# vga_fpga.net
KiCad netlist of a schematic drawn in EAGLE
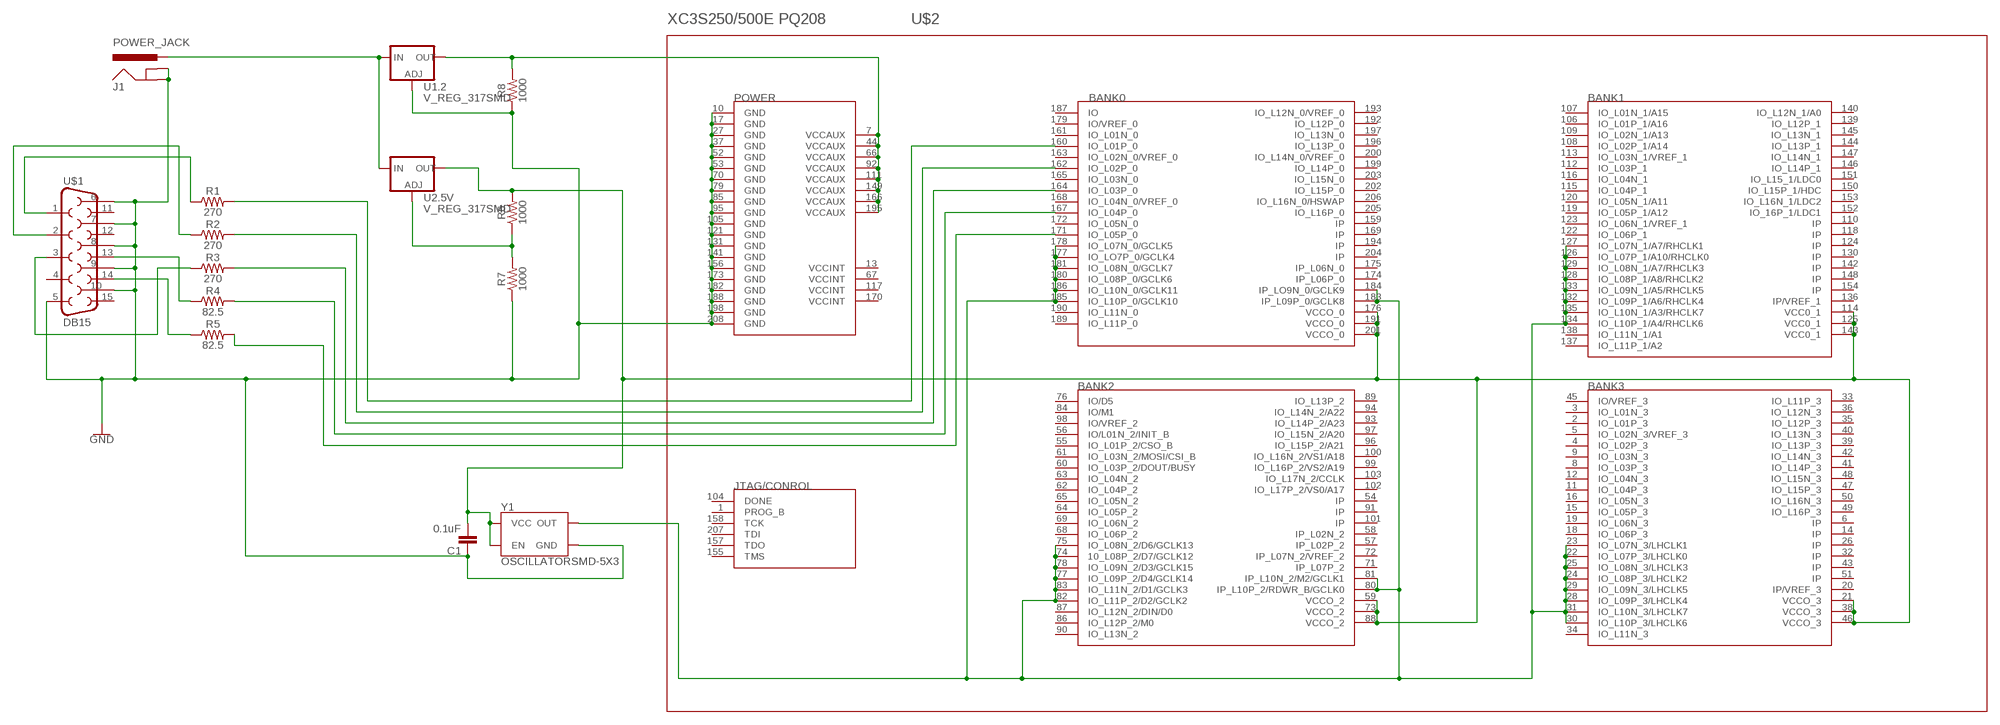
[diagram p0: schematic, sheet 1]

(export (version "E")
  (design (tool "Eeschema 10.0.6"))
  (components
    (comp (ref "C1")
      (value "0.1uF")
      (footprint "eagle-import:0603")
      (libsource (lib "eagle-import") (part "0.1UF-0603-25V-(+80/-20%)"))
    )
    (comp (ref "J1")
      (value "POWER_JACK")
      (footprint "eagle-import:POWER_JACK_PTH")
      (libsource (lib "eagle-import") (part "POWER_JACK"))
    )
    (comp (ref "R1")
      (value "270")
      (footprint "eagle-import:0603")
      (libsource (lib "eagle-import") (part "RESISTOR0603"))
    )
    (comp (ref "R2")
      (value "270")
      (footprint "eagle-import:0603")
      (libsource (lib "eagle-import") (part "RESISTOR0603"))
    )
    (comp (ref "R3")
      (value "270")
      (footprint "eagle-import:0603")
      (libsource (lib "eagle-import") (part "RESISTOR0603"))
    )
    (comp (ref "R4")
      (value "82.5")
      (footprint "eagle-import:0603")
      (libsource (lib "eagle-import") (part "RESISTOR0603"))
    )
    (comp (ref "R5")
      (value "82.5")
      (footprint "eagle-import:0603")
      (libsource (lib "eagle-import") (part "RESISTOR0603"))
    )
    (comp (ref "R6")
      (value "1000")
      (footprint "eagle-import:0603")
      (libsource (lib "eagle-import") (part "RESISTOR0603"))
    )
    (comp (ref "R7")
      (value "1000")
      (footprint "eagle-import:0603")
      (libsource (lib "eagle-import") (part "RESISTOR0603"))
    )
    (comp (ref "R8")
      (value "1000")
      (footprint "eagle-import:0603")
      (libsource (lib "eagle-import") (part "RESISTOR0603"))
    )
    (comp (ref "U$1")
      (value "DB15")
      (footprint "eagle-import:DB15")
      (libsource (lib "eagle-import") (part "DB15"))
    )
    (comp (ref "U$2")
      (value "XC3S250/500E-PQ208")
      (footprint "eagle-import:PQ208")
      (libsource (lib "eagle-import") (part "XC3S250/500E-PQ208"))
    )
    (comp (ref "U1.2")
      (value "V_REG_317SMD")
      (footprint "eagle-import:SOT223")
      (libsource (lib "eagle-import") (part "V_REG_317SMD"))
    )
    (comp (ref "U2.5V")
      (value "V_REG_317SMD")
      (footprint "eagle-import:SOT223")
      (libsource (lib "eagle-import") (part "V_REG_317SMD"))
    )
    (comp (ref "Y1")
      (value "OSCILLATORSMD-5X3")
      (footprint "eagle-import:OSCILLATOR-SMD-5X3.2")
      (libsource (lib "eagle-import") (part "OSCILLATORSMD-5X3"))
    )
  )
  (nets
    (net (code "1") (name "GND") (class "Default")
      (node (ref "C1") (pin "1") (pinfunction "1_1") (pintype "passive"))
      (node (ref "J1") (pin "GND") (pinfunction "GND_GND") (pintype "bidirectional"))
      (node (ref "J1") (pin "GNDBREAK") (pinfunction "GNDBREAK_GNDBREAK") (pintype "bidirectional"))
      (node (ref "R7") (pin "1") (pinfunction "1_1") (pintype "passive"))
      (node (ref "R8") (pin "1") (pinfunction "1_1") (pintype "passive"))
      (node (ref "U$1") (pin "10") (pinfunction "10_10") (pintype "passive"))
      (node (ref "U$1") (pin "5") (pinfunction "5_5") (pintype "passive"))
      (node (ref "U$1") (pin "6") (pinfunction "6_6") (pintype "passive"))
      (node (ref "U$1") (pin "7") (pinfunction "7_7") (pintype "passive"))
      (node (ref "U$1") (pin "8") (pinfunction "8_8") (pintype "passive"))
      (node (ref "U$1") (pin "9") (pinfunction "9_9") (pintype "passive"))
      (node (ref "U$2") (pin "10") (pinfunction "GND_10") (pintype "bidirectional"))
      (node (ref "U$2") (pin "105") (pinfunction "GND_105") (pintype "bidirectional"))
      (node (ref "U$2") (pin "121") (pinfunction "GND_121") (pintype "bidirectional"))
      (node (ref "U$2") (pin "131") (pinfunction "GND_131") (pintype "bidirectional"))
      (node (ref "U$2") (pin "141") (pinfunction "GND_141") (pintype "bidirectional"))
      (node (ref "U$2") (pin "156") (pinfunction "GND_156") (pintype "bidirectional"))
      (node (ref "U$2") (pin "17") (pinfunction "GND_17") (pintype "bidirectional"))
      (node (ref "U$2") (pin "173") (pinfunction "GND_173") (pintype "bidirectional"))
      (node (ref "U$2") (pin "182") (pinfunction "GND_182") (pintype "bidirectional"))
      (node (ref "U$2") (pin "188") (pinfunction "GND_188") (pintype "bidirectional"))
      (node (ref "U$2") (pin "198") (pinfunction "GND_198") (pintype "bidirectional"))
      (node (ref "U$2") (pin "208") (pinfunction "GND_208") (pintype "bidirectional"))
      (node (ref "U$2") (pin "27") (pinfunction "GND_27") (pintype "bidirectional"))
      (node (ref "U$2") (pin "37") (pinfunction "GND_37") (pintype "bidirectional"))
      (node (ref "U$2") (pin "52") (pinfunction "GND_52") (pintype "bidirectional"))
      (node (ref "U$2") (pin "53") (pinfunction "GND_53") (pintype "bidirectional"))
      (node (ref "U$2") (pin "70") (pinfunction "GND_70") (pintype "bidirectional"))
      (node (ref "U$2") (pin "79") (pinfunction "GND_79") (pintype "bidirectional"))
      (node (ref "U$2") (pin "85") (pinfunction "GND_85") (pintype "bidirectional"))
      (node (ref "U$2") (pin "95") (pinfunction "GND_95") (pintype "bidirectional"))
      (node (ref "U1.2") (pin "1") (pinfunction "ADJ_1") (pintype "input"))
      (node (ref "Y1") (pin "2") (pinfunction "GND_2") (pintype "bidirectional"))
    )
    (net (code "2") (name "Net-(R1-Pad1)") (class "Default")
      (node (ref "R1") (pin "1") (pinfunction "1_1") (pintype "passive"))
      (node (ref "U$1") (pin "1") (pinfunction "1_1") (pintype "passive"))
    )
    (net (code "3") (name "Net-(R2-Pad1)") (class "Default")
      (node (ref "R2") (pin "1") (pinfunction "1_1") (pintype "passive"))
      (node (ref "U$1") (pin "2") (pinfunction "2_2") (pintype "passive"))
    )
    (net (code "4") (name "Net-(R3-Pad1)") (class "Default")
      (node (ref "R3") (pin "1") (pinfunction "1_1") (pintype "passive"))
      (node (ref "U$1") (pin "3") (pinfunction "3_3") (pintype "passive"))
    )
    (net (code "5") (name "Net-(R4-Pad1)") (class "Default")
      (node (ref "R4") (pin "1") (pinfunction "1_1") (pintype "passive"))
      (node (ref "U$1") (pin "13") (pinfunction "13_13") (pintype "passive"))
    )
    (net (code "6") (name "Net-(R5-Pad1)") (class "Default")
      (node (ref "R5") (pin "1") (pinfunction "1_1") (pintype "passive"))
      (node (ref "U$1") (pin "14") (pinfunction "14_14") (pintype "passive"))
    )
    (net (code "7") (name "Net-(U$2-10_L08P_2{slash}D7{slash}GCLK12)") (class "Default")
      (node (ref "U$2") (pin "126") (pinfunction "IO_L07P_1/A10/RHCLK0_126") (pintype "bidirectional"))
      (node (ref "U$2") (pin "127") (pinfunction "IO_L07N_1/A7/RHCLK1_127") (pintype "bidirectional"))
      (node (ref "U$2") (pin "128") (pinfunction "IO_L08P_1/A8/RHCLK2_128") (pintype "bidirectional"))
      (node (ref "U$2") (pin "129") (pinfunction "IO_L08N_1/A7/RHCLK3_129") (pintype "bidirectional"))
      (node (ref "U$2") (pin "132") (pinfunction "IO_L09P_1/A6/RHCLK4_132") (pintype "bidirectional"))
      (node (ref "U$2") (pin "133") (pinfunction "IO_L09N_1/A5/RHCLK5_133") (pintype "bidirectional"))
      (node (ref "U$2") (pin "134") (pinfunction "IO_L10P_1/A4/RHCLK6_134") (pintype "bidirectional"))
      (node (ref "U$2") (pin "135") (pinfunction "IO_L10N_1/A3/RHCLK7_135") (pintype "bidirectional"))
      (node (ref "U$2") (pin "177") (pinfunction "IO_LO7P_0/GCLK4_177") (pintype "bidirectional"))
      (node (ref "U$2") (pin "178") (pinfunction "IO_L07N_0/GCLK5_178") (pintype "bidirectional"))
      (node (ref "U$2") (pin "180") (pinfunction "IO_L08P_0/GCLK6_180") (pintype "bidirectional"))
      (node (ref "U$2") (pin "181") (pinfunction "IO_L08N_0/GCLK7_181") (pintype "bidirectional"))
      (node (ref "U$2") (pin "183") (pinfunction "IP_L09P_0/GCLK8_183") (pintype "bidirectional"))
      (node (ref "U$2") (pin "184") (pinfunction "IP_LO9N_0/GCLK9_184") (pintype "bidirectional"))
      (node (ref "U$2") (pin "185") (pinfunction "IO_L10P_0/GCLK10_185") (pintype "bidirectional"))
      (node (ref "U$2") (pin "186") (pinfunction "IO_L10N_0/GCLK11_186") (pintype "bidirectional"))
      (node (ref "U$2") (pin "22") (pinfunction "IO_L07P_3/LHCLK0_22") (pintype "bidirectional"))
      (node (ref "U$2") (pin "23") (pinfunction "IO_L07N_3/LHCLK1_23") (pintype "bidirectional"))
      (node (ref "U$2") (pin "24") (pinfunction "IO_L08P_3/LHCLK2_24") (pintype "bidirectional"))
      (node (ref "U$2") (pin "25") (pinfunction "IO_L08N_3/LHCLK3_25") (pintype "bidirectional"))
      (node (ref "U$2") (pin "28") (pinfunction "IO_L09P_3/LHCLK4_28") (pintype "bidirectional"))
      (node (ref "U$2") (pin "29") (pinfunction "IO_L09N_3/LHCLK5_29") (pintype "bidirectional"))
      (node (ref "U$2") (pin "30") (pinfunction "IO_L10P_3/LHCLK6_30") (pintype "bidirectional"))
      (node (ref "U$2") (pin "31") (pinfunction "IO_L10N_3/LHCLK7_31") (pintype "bidirectional"))
      (node (ref "U$2") (pin "74") (pinfunction "10_L08P_2/D7/GCLK12_74") (pintype "bidirectional"))
      (node (ref "U$2") (pin "75") (pinfunction "IO_L08N_2/D6/GCLK13_75") (pintype "bidirectional"))
      (node (ref "U$2") (pin "77") (pinfunction "IO_L09P_2/D4/GCLK14_77") (pintype "bidirectional"))
      (node (ref "U$2") (pin "78") (pinfunction "IO_L09N_2/D3/GCLK15_78") (pintype "bidirectional"))
      (node (ref "U$2") (pin "80") (pinfunction "IP_L10P_2/RDWR_B/GCLK0_80") (pintype "bidirectional"))
      (node (ref "U$2") (pin "81") (pinfunction "IP_L10N_2/M2/GCLK1_81") (pintype "bidirectional"))
      (node (ref "U$2") (pin "82") (pinfunction "IO_L11P_2/D2/GCLK2_82") (pintype "bidirectional"))
      (node (ref "U$2") (pin "83") (pinfunction "IO_L11N_2/D1/GCLK3_83") (pintype "bidirectional"))
      (node (ref "Y1") (pin "3") (pinfunction "OUT_3") (pintype "bidirectional"))
    )
    (net (code "8") (name "Net-(U$2-IO_L01P_0)") (class "Default")
      (node (ref "R1") (pin "2") (pinfunction "2_2") (pintype "passive"))
      (node (ref "U$2") (pin "160") (pinfunction "IO_L01P_0_160") (pintype "bidirectional"))
    )
    (net (code "9") (name "Net-(U$2-IO_L02P_0)") (class "Default")
      (node (ref "R2") (pin "2") (pinfunction "2_2") (pintype "passive"))
      (node (ref "U$2") (pin "162") (pinfunction "IO_L02P_0_162") (pintype "bidirectional"))
    )
    (net (code "10") (name "Net-(U$2-IO_L03P_0)") (class "Default")
      (node (ref "R3") (pin "2") (pinfunction "2_2") (pintype "passive"))
      (node (ref "U$2") (pin "164") (pinfunction "IO_L03P_0_164") (pintype "bidirectional"))
    )
    (net (code "11") (name "Net-(U$2-IO_L04P_0)") (class "Default")
      (node (ref "R4") (pin "2") (pinfunction "2_2") (pintype "passive"))
      (node (ref "U$2") (pin "167") (pinfunction "IO_L04P_0_167") (pintype "bidirectional"))
    )
    (net (code "12") (name "Net-(U$2-IO_L05P_0)") (class "Default")
      (node (ref "R5") (pin "2") (pinfunction "2_2") (pintype "passive"))
      (node (ref "U$2") (pin "171") (pinfunction "IO_L05P_0_171") (pintype "bidirectional"))
    )
    (net (code "13") (name "Net-(U1.2-IN)") (class "Default")
      (node (ref "J1") (pin "PWR") (pinfunction "PWR_PWR") (pintype "bidirectional"))
      (node (ref "U1.2") (pin "3") (pinfunction "IN_3") (pintype "input"))
      (node (ref "U2.5V") (pin "3") (pinfunction "IN_3") (pintype "input"))
    )
    (net (code "14") (name "Net-(U1.2-OUT)") (class "Default")
      (node (ref "R8") (pin "2") (pinfunction "2_2") (pintype "passive"))
      (node (ref "U$2") (pin "111") (pinfunction "VCCAUX_111") (pintype "bidirectional"))
      (node (ref "U$2") (pin "149") (pinfunction "VCCAUX_149") (pintype "bidirectional"))
      (node (ref "U$2") (pin "166") (pinfunction "VCCAUX_166") (pintype "bidirectional"))
      (node (ref "U$2") (pin "195") (pinfunction "VCCAUX_195") (pintype "bidirectional"))
      (node (ref "U$2") (pin "44") (pinfunction "VCCAUX_44") (pintype "bidirectional"))
      (node (ref "U$2") (pin "66") (pinfunction "VCCAUX_66") (pintype "bidirectional"))
      (node (ref "U$2") (pin "7") (pinfunction "VCCAUX_7") (pintype "bidirectional"))
      (node (ref "U$2") (pin "92") (pinfunction "VCCAUX_92") (pintype "bidirectional"))
      (node (ref "U1.2") (pin "2") (pinfunction "OUT_2") (pintype "output"))
    )
    (net (code "15") (name "Net-(U2.5V-ADJ)") (class "Default")
      (node (ref "R6") (pin "1") (pinfunction "1_1") (pintype "passive"))
      (node (ref "R7") (pin "2") (pinfunction "2_2") (pintype "passive"))
      (node (ref "U2.5V") (pin "1") (pinfunction "ADJ_1") (pintype "input"))
    )
    (net (code "16") (name "Net-(U2.5V-OUT)") (class "Default")
      (node (ref "C1") (pin "2") (pinfunction "2_2") (pintype "passive"))
      (node (ref "R6") (pin "2") (pinfunction "2_2") (pintype "passive"))
      (node (ref "U$2") (pin "114") (pinfunction "VCC0_1_114") (pintype "bidirectional"))
      (node (ref "U$2") (pin "125") (pinfunction "VCC0_1_125") (pintype "bidirectional"))
      (node (ref "U$2") (pin "143") (pinfunction "VCC0_1_143") (pintype "bidirectional"))
      (node (ref "U$2") (pin "176") (pinfunction "VCCO_0_176") (pintype "bidirectional"))
      (node (ref "U$2") (pin "191") (pinfunction "VCCO_0_191") (pintype "bidirectional"))
      (node (ref "U$2") (pin "201") (pinfunction "VCCO_0_201") (pintype "bidirectional"))
      (node (ref "U$2") (pin "21") (pinfunction "VCCO_3_21") (pintype "bidirectional"))
      (node (ref "U$2") (pin "38") (pinfunction "VCCO_3_38") (pintype "bidirectional"))
      (node (ref "U$2") (pin "46") (pinfunction "VCCO_3_46") (pintype "bidirectional"))
      (node (ref "U$2") (pin "59") (pinfunction "VCCO_2_59") (pintype "bidirectional"))
      (node (ref "U$2") (pin "73") (pinfunction "VCCO_2_73") (pintype "bidirectional"))
      (node (ref "U$2") (pin "88") (pinfunction "VCCO_2_88") (pintype "bidirectional"))
      (node (ref "U2.5V") (pin "2") (pinfunction "OUT_2") (pintype "output"))
      (node (ref "Y1") (pin "1") (pinfunction "EN_1") (pintype "bidirectional"))
      (node (ref "Y1") (pin "4") (pinfunction "VCC_4") (pintype "bidirectional"))
    )
    (net (code "17") (name "unconnected-(U$1-Pad4)") (class "Default")
      (node (ref "U$1") (pin "4") (pinfunction "4_4") (pintype "passive"))
    )
    (net (code "18") (name "unconnected-(U$1-Pad11)") (class "Default")
      (node (ref "U$1") (pin "11") (pinfunction "11_11") (pintype "passive"))
    )
    (net (code "19") (name "unconnected-(U$1-Pad12)") (class "Default")
      (node (ref "U$1") (pin "12") (pinfunction "12_12") (pintype "passive"))
    )
    (net (code "20") (name "unconnected-(U$1-Pad15)") (class "Default")
      (node (ref "U$1") (pin "15") (pinfunction "15_15") (pintype "passive"))
    )
    (net (code "21") (name "unconnected-(U$2-DONE-Pad104)") (class "Default")
      (node (ref "U$2") (pin "104") (pinfunction "DONE_104") (pintype "bidirectional"))
    )
    (net (code "22") (name "unconnected-(U$2-IO-Pad187)") (class "Default")
      (node (ref "U$2") (pin "187") (pinfunction "IO_187") (pintype "bidirectional"))
    )
    (net (code "23") (name "unconnected-(U$2-IO_16P_1{slash}LDC1-Pad152)") (class "Default")
      (node (ref "U$2") (pin "152") (pinfunction "IO_16P_1/LDC1_152") (pintype "bidirectional"))
    )
    (net (code "24") (name "unconnected-(U$2-IO_L01N_0-Pad161)") (class "Default")
      (node (ref "U$2") (pin "161") (pinfunction "IO_L01N_0_161") (pintype "bidirectional"))
    )
    (net (code "25") (name "unconnected-(U$2-IO_L01N_1{slash}A15-Pad107)") (class "Default")
      (node (ref "U$2") (pin "107") (pinfunction "IO_L01N_1/A15_107") (pintype "bidirectional"))
    )
    (net (code "26") (name "unconnected-(U$2-IO_L01N_3-Pad3)") (class "Default")
      (node (ref "U$2") (pin "3") (pinfunction "IO_L01N_3_3") (pintype "bidirectional"))
    )
    (net (code "27") (name "unconnected-(U$2-IO_L01P_1{slash}A16-Pad106)") (class "Default")
      (node (ref "U$2") (pin "106") (pinfunction "IO_L01P_1/A16_106") (pintype "bidirectional"))
    )
    (net (code "28") (name "unconnected-(U$2-IO_L01P_2{slash}CSO_B-Pad55)") (class "Default")
      (node (ref "U$2") (pin "55") (pinfunction "IO_L01P_2/CSO_B_55") (pintype "bidirectional"))
    )
    (net (code "29") (name "unconnected-(U$2-IO_L01P_3-Pad2)") (class "Default")
      (node (ref "U$2") (pin "2") (pinfunction "IO_L01P_3_2") (pintype "bidirectional"))
    )
    (net (code "30") (name "unconnected-(U$2-IO_L02N_0{slash}VREF_0-Pad163)") (class "Default")
      (node (ref "U$2") (pin "163") (pinfunction "IO_L02N_0/VREF_0_163") (pintype "bidirectional"))
    )
    (net (code "31") (name "unconnected-(U$2-IO_L02N_1{slash}A13-Pad109)") (class "Default")
      (node (ref "U$2") (pin "109") (pinfunction "IO_L02N_1/A13_109") (pintype "bidirectional"))
    )
    (net (code "32") (name "unconnected-(U$2-IO_L02N_3{slash}VREF_3-Pad5)") (class "Default")
      (node (ref "U$2") (pin "5") (pinfunction "IO_L02N_3/VREF_3_5") (pintype "bidirectional"))
    )
    (net (code "33") (name "unconnected-(U$2-IO_L02P_1{slash}A14-Pad108)") (class "Default")
      (node (ref "U$2") (pin "108") (pinfunction "IO_L02P_1/A14_108") (pintype "bidirectional"))
    )
    (net (code "34") (name "unconnected-(U$2-IO_L02P_3-Pad4)") (class "Default")
      (node (ref "U$2") (pin "4") (pinfunction "IO_L02P_3_4") (pintype "bidirectional"))
    )
    (net (code "35") (name "unconnected-(U$2-IO_L03N_0-Pad165)") (class "Default")
      (node (ref "U$2") (pin "165") (pinfunction "IO_L03N_0_165") (pintype "bidirectional"))
    )
    (net (code "36") (name "unconnected-(U$2-IO_L03N_1{slash}VREF_1-Pad113)") (class "Default")
      (node (ref "U$2") (pin "113") (pinfunction "IO_L03N_1/VREF_1_113") (pintype "bidirectional"))
    )
    (net (code "37") (name "unconnected-(U$2-IO_L03N_2{slash}MOSI{slash}CSI_B-Pad61)") (class "Default")
      (node (ref "U$2") (pin "61") (pinfunction "IO_L03N_2/MOSI/CSI_B_61") (pintype "bidirectional"))
    )
    (net (code "38") (name "unconnected-(U$2-IO_L03N_3-Pad9)") (class "Default")
      (node (ref "U$2") (pin "9") (pinfunction "IO_L03N_3_9") (pintype "bidirectional"))
    )
    (net (code "39") (name "unconnected-(U$2-IO_L03P_1-Pad112)") (class "Default")
      (node (ref "U$2") (pin "112") (pinfunction "IO_L03P_1_112") (pintype "bidirectional"))
    )
    (net (code "40") (name "unconnected-(U$2-IO_L03P_2{slash}DOUT{slash}BUSY-Pad60)") (class "Default")
      (node (ref "U$2") (pin "60") (pinfunction "IO_L03P_2/DOUT/BUSY_60") (pintype "bidirectional"))
    )
    (net (code "41") (name "unconnected-(U$2-IO_L03P_3-Pad8)") (class "Default")
      (node (ref "U$2") (pin "8") (pinfunction "IO_L03P_3_8") (pintype "bidirectional"))
    )
    (net (code "42") (name "unconnected-(U$2-IO_L04N_0{slash}VREF_0-Pad168)") (class "Default")
      (node (ref "U$2") (pin "168") (pinfunction "IO_L04N_0/VREF_0_168") (pintype "bidirectional"))
    )
    (net (code "43") (name "unconnected-(U$2-IO_L04N_1-Pad116)") (class "Default")
      (node (ref "U$2") (pin "116") (pinfunction "IO_L04N_1_116") (pintype "bidirectional"))
    )
    (net (code "44") (name "unconnected-(U$2-IO_L04N_2-Pad63)") (class "Default")
      (node (ref "U$2") (pin "63") (pinfunction "IO_L04N_2_63") (pintype "bidirectional"))
    )
    (net (code "45") (name "unconnected-(U$2-IO_L04N_3-Pad12)") (class "Default")
      (node (ref "U$2") (pin "12") (pinfunction "IO_L04N_3_12") (pintype "bidirectional"))
    )
    (net (code "46") (name "unconnected-(U$2-IO_L04P_1-Pad115)") (class "Default")
      (node (ref "U$2") (pin "115") (pinfunction "IO_L04P_1_115") (pintype "bidirectional"))
    )
    (net (code "47") (name "unconnected-(U$2-IO_L04P_2-Pad62)") (class "Default")
      (node (ref "U$2") (pin "62") (pinfunction "IO_L04P_2_62") (pintype "bidirectional"))
    )
    (net (code "48") (name "unconnected-(U$2-IO_L04P_3-Pad11)") (class "Default")
      (node (ref "U$2") (pin "11") (pinfunction "IO_L04P_3_11") (pintype "bidirectional"))
    )
    (net (code "49") (name "unconnected-(U$2-IO_L05N_0-Pad172)") (class "Default")
      (node (ref "U$2") (pin "172") (pinfunction "IO_L05N_0_172") (pintype "bidirectional"))
    )
    (net (code "50") (name "unconnected-(U$2-IO_L05N_1{slash}A11-Pad120)") (class "Default")
      (node (ref "U$2") (pin "120") (pinfunction "IO_L05N_1/A11_120") (pintype "bidirectional"))
    )
    (net (code "51") (name "unconnected-(U$2-IO_L05N_2-Pad65)") (class "Default")
      (node (ref "U$2") (pin "65") (pinfunction "IO_L05N_2_65") (pintype "bidirectional"))
    )
    (net (code "52") (name "unconnected-(U$2-IO_L05N_3-Pad16)") (class "Default")
      (node (ref "U$2") (pin "16") (pinfunction "IO_L05N_3_16") (pintype "bidirectional"))
    )
    (net (code "53") (name "unconnected-(U$2-IO_L05P_1{slash}A12-Pad119)") (class "Default")
      (node (ref "U$2") (pin "119") (pinfunction "IO_L05P_1/A12_119") (pintype "bidirectional"))
    )
    (net (code "54") (name "unconnected-(U$2-IO_L05P_2-Pad64)") (class "Default")
      (node (ref "U$2") (pin "64") (pinfunction "IO_L05P_2_64") (pintype "bidirectional"))
    )
    (net (code "55") (name "unconnected-(U$2-IO_L05P_3-Pad15)") (class "Default")
      (node (ref "U$2") (pin "15") (pinfunction "IO_L05P_3_15") (pintype "bidirectional"))
    )
    (net (code "56") (name "unconnected-(U$2-IO_L06N_1{slash}VREF_1-Pad123)") (class "Default")
      (node (ref "U$2") (pin "123") (pinfunction "IO_L06N_1/VREF_1_123") (pintype "bidirectional"))
    )
    (net (code "57") (name "unconnected-(U$2-IO_L06N_2-Pad69)") (class "Default")
      (node (ref "U$2") (pin "69") (pinfunction "IO_L06N_2_69") (pintype "bidirectional"))
    )
    (net (code "58") (name "unconnected-(U$2-IO_L06N_3-Pad19)") (class "Default")
      (node (ref "U$2") (pin "19") (pinfunction "IO_L06N_3_19") (pintype "bidirectional"))
    )
    (net (code "59") (name "unconnected-(U$2-IO_L06P_1-Pad122)") (class "Default")
      (node (ref "U$2") (pin "122") (pinfunction "IO_L06P_1_122") (pintype "bidirectional"))
    )
    (net (code "60") (name "unconnected-(U$2-IO_L06P_2-Pad68)") (class "Default")
      (node (ref "U$2") (pin "68") (pinfunction "IO_L06P_2_68") (pintype "bidirectional"))
    )
    (net (code "61") (name "unconnected-(U$2-IO_L06P_3-Pad18)") (class "Default")
      (node (ref "U$2") (pin "18") (pinfunction "IO_L06P_3_18") (pintype "bidirectional"))
    )
    (net (code "62") (name "unconnected-(U$2-IO_L11N_0-Pad190)") (class "Default")
      (node (ref "U$2") (pin "190") (pinfunction "IO_L11N_0_190") (pintype "bidirectional"))
    )
    (net (code "63") (name "unconnected-(U$2-IO_L11N_1{slash}A1-Pad138)") (class "Default")
      (node (ref "U$2") (pin "138") (pinfunction "IO_L11N_1/A1_138") (pintype "bidirectional"))
    )
    (net (code "64") (name "unconnected-(U$2-IO_L11N_3-Pad34)") (class "Default")
      (node (ref "U$2") (pin "34") (pinfunction "IO_L11N_3_34") (pintype "bidirectional"))
    )
    (net (code "65") (name "unconnected-(U$2-IO_L11P_0-Pad189)") (class "Default")
      (node (ref "U$2") (pin "189") (pinfunction "IO_L11P_0_189") (pintype "bidirectional"))
    )
    (net (code "66") (name "unconnected-(U$2-IO_L11P_1{slash}A2-Pad137)") (class "Default")
      (node (ref "U$2") (pin "137") (pinfunction "IO_L11P_1/A2_137") (pintype "bidirectional"))
    )
    (net (code "67") (name "unconnected-(U$2-IO_L11P_3-Pad33)") (class "Default")
      (node (ref "U$2") (pin "33") (pinfunction "IO_L11P_3_33") (pintype "bidirectional"))
    )
    (net (code "68") (name "unconnected-(U$2-IO_L12N_0{slash}VREF_0-Pad193)") (class "Default")
      (node (ref "U$2") (pin "193") (pinfunction "IO_L12N_0/VREF_0_193") (pintype "bidirectional"))
    )
    (net (code "69") (name "unconnected-(U$2-IO_L12N_1{slash}A0-Pad140)") (class "Default")
      (node (ref "U$2") (pin "140") (pinfunction "IO_L12N_1/A0_140") (pintype "bidirectional"))
    )
    (net (code "70") (name "unconnected-(U$2-IO_L12N_2{slash}DIN{slash}D0-Pad87)") (class "Default")
      (node (ref "U$2") (pin "87") (pinfunction "IO_L12N_2/DIN/D0_87") (pintype "bidirectional"))
    )
    (net (code "71") (name "unconnected-(U$2-IO_L12N_3-Pad36)") (class "Default")
      (node (ref "U$2") (pin "36") (pinfunction "IO_L12N_3_36") (pintype "bidirectional"))
    )
    (net (code "72") (name "unconnected-(U$2-IO_L12P_0-Pad192)") (class "Default")
      (node (ref "U$2") (pin "192") (pinfunction "IO_L12P_0_192") (pintype "bidirectional"))
    )
    (net (code "73") (name "unconnected-(U$2-IO_L12P_1-Pad139)") (class "Default")
      (node (ref "U$2") (pin "139") (pinfunction "IO_L12P_1_139") (pintype "bidirectional"))
    )
    (net (code "74") (name "unconnected-(U$2-IO_L12P_2{slash}M0-Pad86)") (class "Default")
      (node (ref "U$2") (pin "86") (pinfunction "IO_L12P_2/M0_86") (pintype "bidirectional"))
    )
    (net (code "75") (name "unconnected-(U$2-IO_L12P_3-Pad35)") (class "Default")
      (node (ref "U$2") (pin "35") (pinfunction "IO_L12P_3_35") (pintype "bidirectional"))
    )
    (net (code "76") (name "unconnected-(U$2-IO_L13N_0-Pad197)") (class "Default")
      (node (ref "U$2") (pin "197") (pinfunction "IO_L13N_0_197") (pintype "bidirectional"))
    )
    (net (code "77") (name "unconnected-(U$2-IO_L13N_1-Pad145)") (class "Default")
      (node (ref "U$2") (pin "145") (pinfunction "IO_L13N_1_145") (pintype "bidirectional"))
    )
    (net (code "78") (name "unconnected-(U$2-IO_L13N_2-Pad90)") (class "Default")
      (node (ref "U$2") (pin "90") (pinfunction "IO_L13N_2_90") (pintype "bidirectional"))
    )
    (net (code "79") (name "unconnected-(U$2-IO_L13N_3-Pad40)") (class "Default")
      (node (ref "U$2") (pin "40") (pinfunction "IO_L13N_3_40") (pintype "bidirectional"))
    )
    (net (code "80") (name "unconnected-(U$2-IO_L13P_0-Pad196)") (class "Default")
      (node (ref "U$2") (pin "196") (pinfunction "IO_L13P_0_196") (pintype "bidirectional"))
    )
    (net (code "81") (name "unconnected-(U$2-IO_L13P_1-Pad144)") (class "Default")
      (node (ref "U$2") (pin "144") (pinfunction "IO_L13P_1_144") (pintype "bidirectional"))
    )
    (net (code "82") (name "unconnected-(U$2-IO_L13P_2-Pad89)") (class "Default")
      (node (ref "U$2") (pin "89") (pinfunction "IO_L13P_2_89") (pintype "bidirectional"))
    )
    (net (code "83") (name "unconnected-(U$2-IO_L13P_3-Pad39)") (class "Default")
      (node (ref "U$2") (pin "39") (pinfunction "IO_L13P_3_39") (pintype "bidirectional"))
    )
    (net (code "84") (name "unconnected-(U$2-IO_L14N_0{slash}VREF_0-Pad200)") (class "Default")
      (node (ref "U$2") (pin "200") (pinfunction "IO_L14N_0/VREF_0_200") (pintype "bidirectional"))
    )
    (net (code "85") (name "unconnected-(U$2-IO_L14N_1-Pad147)") (class "Default")
      (node (ref "U$2") (pin "147") (pinfunction "IO_L14N_1_147") (pintype "bidirectional"))
    )
    (net (code "86") (name "unconnected-(U$2-IO_L14N_2{slash}A22-Pad94)") (class "Default")
      (node (ref "U$2") (pin "94") (pinfunction "IO_L14N_2/A22_94") (pintype "bidirectional"))
    )
    (net (code "87") (name "unconnected-(U$2-IO_L14N_3-Pad42)") (class "Default")
      (node (ref "U$2") (pin "42") (pinfunction "IO_L14N_3_42") (pintype "bidirectional"))
    )
    (net (code "88") (name "unconnected-(U$2-IO_L14P_0-Pad199)") (class "Default")
      (node (ref "U$2") (pin "199") (pinfunction "IO_L14P_0_199") (pintype "bidirectional"))
    )
    (net (code "89") (name "unconnected-(U$2-IO_L14P_1-Pad146)") (class "Default")
      (node (ref "U$2") (pin "146") (pinfunction "IO_L14P_1_146") (pintype "bidirectional"))
    )
    (net (code "90") (name "unconnected-(U$2-IO_L14P_2{slash}A23-Pad93)") (class "Default")
      (node (ref "U$2") (pin "93") (pinfunction "IO_L14P_2/A23_93") (pintype "bidirectional"))
    )
    (net (code "91") (name "unconnected-(U$2-IO_L14P_3-Pad41)") (class "Default")
      (node (ref "U$2") (pin "41") (pinfunction "IO_L14P_3_41") (pintype "bidirectional"))
    )
    (net (code "92") (name "unconnected-(U$2-IO_L15N_0-Pad203)") (class "Default")
      (node (ref "U$2") (pin "203") (pinfunction "IO_L15N_0_203") (pintype "bidirectional"))
    )
    (net (code "93") (name "unconnected-(U$2-IO_L15N_2{slash}A20-Pad97)") (class "Default")
      (node (ref "U$2") (pin "97") (pinfunction "IO_L15N_2/A20_97") (pintype "bidirectional"))
    )
    (net (code "94") (name "unconnected-(U$2-IO_L15N_3-Pad48)") (class "Default")
      (node (ref "U$2") (pin "48") (pinfunction "IO_L15N_3_48") (pintype "bidirectional"))
    )
    (net (code "95") (name "unconnected-(U$2-IO_L15P_0-Pad202)") (class "Default")
      (node (ref "U$2") (pin "202") (pinfunction "IO_L15P_0_202") (pintype "bidirectional"))
    )
    (net (code "96") (name "unconnected-(U$2-IO_L15P_1{slash}HDC-Pad150)") (class "Default")
      (node (ref "U$2") (pin "150") (pinfunction "IO_L15P_1/HDC_150") (pintype "bidirectional"))
    )
    (net (code "97") (name "unconnected-(U$2-IO_L15P_2{slash}A21-Pad96)") (class "Default")
      (node (ref "U$2") (pin "96") (pinfunction "IO_L15P_2/A21_96") (pintype "bidirectional"))
    )
    (net (code "98") (name "unconnected-(U$2-IO_L15P_3-Pad47)") (class "Default")
      (node (ref "U$2") (pin "47") (pinfunction "IO_L15P_3_47") (pintype "bidirectional"))
    )
    (net (code "99") (name "unconnected-(U$2-IO_L15_1{slash}LDC0-Pad151)") (class "Default")
      (node (ref "U$2") (pin "151") (pinfunction "IO_L15_1/LDC0_151") (pintype "bidirectional"))
    )
    (net (code "100") (name "unconnected-(U$2-IO_L16N_0{slash}HSWAP-Pad206)") (class "Default")
      (node (ref "U$2") (pin "206") (pinfunction "IO_L16N_0/HSWAP_206") (pintype "bidirectional"))
    )
    (net (code "101") (name "unconnected-(U$2-IO_L16N_1{slash}LDC2-Pad153)") (class "Default")
      (node (ref "U$2") (pin "153") (pinfunction "IO_L16N_1/LDC2_153") (pintype "bidirectional"))
    )
    (net (code "102") (name "unconnected-(U$2-IO_L16N_2{slash}VS1{slash}A18-Pad100)") (class "Default")
      (node (ref "U$2") (pin "100") (pinfunction "IO_L16N_2/VS1/A18_100") (pintype "bidirectional"))
    )
    (net (code "103") (name "unconnected-(U$2-IO_L16N_3-Pad50)") (class "Default")
      (node (ref "U$2") (pin "50") (pinfunction "IO_L16N_3_50") (pintype "bidirectional"))
    )
    (net (code "104") (name "unconnected-(U$2-IO_L16P_0-Pad205)") (class "Default")
      (node (ref "U$2") (pin "205") (pinfunction "IO_L16P_0_205") (pintype "bidirectional"))
    )
    (net (code "105") (name "unconnected-(U$2-IO_L16P_2{slash}VS2{slash}A19-Pad99)") (class "Default")
      (node (ref "U$2") (pin "99") (pinfunction "IO_L16P_2/VS2/A19_99") (pintype "bidirectional"))
    )
    (net (code "106") (name "unconnected-(U$2-IO_L16P_3-Pad49)") (class "Default")
      (node (ref "U$2") (pin "49") (pinfunction "IO_L16P_3_49") (pintype "bidirectional"))
    )
    (net (code "107") (name "unconnected-(U$2-IO_L17N_2{slash}CCLK-Pad103)") (class "Default")
      (node (ref "U$2") (pin "103") (pinfunction "IO_L17N_2/CCLK_103") (pintype "bidirectional"))
    )
    (net (code "108") (name "unconnected-(U$2-IO_L17P_2{slash}VS0{slash}A17-Pad102)") (class "Default")
      (node (ref "U$2") (pin "102") (pinfunction "IO_L17P_2/VS0/A17_102") (pintype "bidirectional"))
    )
    (net (code "109") (name "unconnected-(U$2-IO{slash}D5-Pad76)") (class "Default")
      (node (ref "U$2") (pin "76") (pinfunction "IO/D5_76") (pintype "bidirectional"))
    )
    (net (code "110") (name "unconnected-(U$2-IO{slash}L01N_2{slash}INIT_B-Pad56)") (class "Default")
      (node (ref "U$2") (pin "56") (pinfunction "IO/L01N_2/INIT_B_56") (pintype "bidirectional"))
    )
    (net (code "111") (name "unconnected-(U$2-IO{slash}M1-Pad84)") (class "Default")
      (node (ref "U$2") (pin "84") (pinfunction "IO/M1_84") (pintype "bidirectional"))
    )
    (net (code "112") (name "unconnected-(U$2-IO{slash}VREF_0-Pad179)") (class "Default")
      (node (ref "U$2") (pin "179") (pinfunction "IO/VREF_0_179") (pintype "bidirectional"))
    )
    (net (code "113") (name "unconnected-(U$2-IO{slash}VREF_2-Pad98)") (class "Default")
      (node (ref "U$2") (pin "98") (pinfunction "IO/VREF_2_98") (pintype "bidirectional"))
    )
    (net (code "114") (name "unconnected-(U$2-IO{slash}VREF_3-Pad45)") (class "Default")
      (node (ref "U$2") (pin "45") (pinfunction "IO/VREF_3_45") (pintype "bidirectional"))
    )
    (net (code "115") (name "unconnected-(U$2-IP-Pad6)") (class "Default")
      (node (ref "U$2") (pin "6") (pinfunction "IP_6") (pintype "bidirectional"))
    )
    (net (code "116") (name "unconnected-(U$2-IP-Pad14)") (class "Default")
      (node (ref "U$2") (pin "14") (pinfunction "IP_14") (pintype "bidirectional"))
    )
    (net (code "117") (name "unconnected-(U$2-IP-Pad26)") (class "Default")
      (node (ref "U$2") (pin "26") (pinfunction "IP_26") (pintype "bidirectional"))
    )
    (net (code "118") (name "unconnected-(U$2-IP-Pad32)") (class "Default")
      (node (ref "U$2") (pin "32") (pinfunction "IP_32") (pintype "bidirectional"))
    )
    (net (code "119") (name "unconnected-(U$2-IP-Pad43)") (class "Default")
      (node (ref "U$2") (pin "43") (pinfunction "IP_43") (pintype "bidirectional"))
    )
    (net (code "120") (name "unconnected-(U$2-IP-Pad51)") (class "Default")
      (node (ref "U$2") (pin "51") (pinfunction "IP_51") (pintype "bidirectional"))
    )
    (net (code "121") (name "unconnected-(U$2-IP-Pad54)") (class "Default")
      (node (ref "U$2") (pin "54") (pinfunction "IP_54") (pintype "bidirectional"))
    )
    (net (code "122") (name "unconnected-(U$2-IP-Pad91)") (class "Default")
      (node (ref "U$2") (pin "91") (pinfunction "IP_91") (pintype "bidirectional"))
    )
    (net (code "123") (name "unconnected-(U$2-IP-Pad101)") (class "Default")
      (node (ref "U$2") (pin "101") (pinfunction "IP_101") (pintype "bidirectional"))
    )
    (net (code "124") (name "unconnected-(U$2-IP-Pad110)") (class "Default")
      (node (ref "U$2") (pin "110") (pinfunction "IP_110") (pintype "bidirectional"))
    )
    (net (code "125") (name "unconnected-(U$2-IP-Pad118)") (class "Default")
      (node (ref "U$2") (pin "118") (pinfunction "IP_118") (pintype "bidirectional"))
    )
    (net (code "126") (name "unconnected-(U$2-IP-Pad124)") (class "Default")
      (node (ref "U$2") (pin "124") (pinfunction "IP_124") (pintype "bidirectional"))
    )
    (net (code "127") (name "unconnected-(U$2-IP-Pad130)") (class "Default")
      (node (ref "U$2") (pin "130") (pinfunction "IP_130") (pintype "bidirectional"))
    )
    (net (code "128") (name "unconnected-(U$2-IP-Pad142)") (class "Default")
      (node (ref "U$2") (pin "142") (pinfunction "IP_142") (pintype "bidirectional"))
    )
    (net (code "129") (name "unconnected-(U$2-IP-Pad148)") (class "Default")
      (node (ref "U$2") (pin "148") (pinfunction "IP_148") (pintype "bidirectional"))
    )
    (net (code "130") (name "unconnected-(U$2-IP-Pad154)") (class "Default")
      (node (ref "U$2") (pin "154") (pinfunction "IP_154") (pintype "bidirectional"))
    )
    (net (code "131") (name "unconnected-(U$2-IP-Pad159)") (class "Default")
      (node (ref "U$2") (pin "159") (pinfunction "IP_159") (pintype "bidirectional"))
    )
    (net (code "132") (name "unconnected-(U$2-IP-Pad169)") (class "Default")
      (node (ref "U$2") (pin "169") (pinfunction "IP_169") (pintype "bidirectional"))
    )
    (net (code "133") (name "unconnected-(U$2-IP-Pad194)") (class "Default")
      (node (ref "U$2") (pin "194") (pinfunction "IP_194") (pintype "bidirectional"))
    )
    (net (code "134") (name "unconnected-(U$2-IP-Pad204)") (class "Default")
      (node (ref "U$2") (pin "204") (pinfunction "IP_204") (pintype "bidirectional"))
    )
    (net (code "135") (name "unconnected-(U$2-IP_L02N_2-Pad58)") (class "Default")
      (node (ref "U$2") (pin "58") (pinfunction "IP_L02N_2_58") (pintype "bidirectional"))
    )
    (net (code "136") (name "unconnected-(U$2-IP_L02P_2-Pad57)") (class "Default")
      (node (ref "U$2") (pin "57") (pinfunction "IP_L02P_2_57") (pintype "bidirectional"))
    )
    (net (code "137") (name "unconnected-(U$2-IP_L06N_0-Pad175)") (class "Default")
      (node (ref "U$2") (pin "175") (pinfunction "IP_L06N_0_175") (pintype "bidirectional"))
    )
    (net (code "138") (name "unconnected-(U$2-IP_L06P_0-Pad174)") (class "Default")
      (node (ref "U$2") (pin "174") (pinfunction "IP_L06P_0_174") (pintype "bidirectional"))
    )
    (net (code "139") (name "unconnected-(U$2-IP_L07N_2{slash}VREF_2-Pad72)") (class "Default")
      (node (ref "U$2") (pin "72") (pinfunction "IP_L07N_2/VREF_2_72") (pintype "bidirectional"))
    )
    (net (code "140") (name "unconnected-(U$2-IP_L07P_2-Pad71)") (class "Default")
      (node (ref "U$2") (pin "71") (pinfunction "IP_L07P_2_71") (pintype "bidirectional"))
    )
    (net (code "141") (name "unconnected-(U$2-IP{slash}VREF_1-Pad136)") (class "Default")
      (node (ref "U$2") (pin "136") (pinfunction "IP/VREF_1_136") (pintype "bidirectional"))
    )
    (net (code "142") (name "unconnected-(U$2-IP{slash}VREF_3-Pad20)") (class "Default")
      (node (ref "U$2") (pin "20") (pinfunction "IP/VREF_3_20") (pintype "bidirectional"))
    )
    (net (code "143") (name "unconnected-(U$2-PROG_B-Pad1)") (class "Default")
      (node (ref "U$2") (pin "1") (pinfunction "PROG_B_1") (pintype "bidirectional"))
    )
    (net (code "144") (name "unconnected-(U$2-TCK-Pad158)") (class "Default")
      (node (ref "U$2") (pin "158") (pinfunction "TCK_158") (pintype "bidirectional"))
    )
    (net (code "145") (name "unconnected-(U$2-TDI-Pad207)") (class "Default")
      (node (ref "U$2") (pin "207") (pinfunction "TDI_207") (pintype "bidirectional"))
    )
    (net (code "146") (name "unconnected-(U$2-TDO-Pad157)") (class "Default")
      (node (ref "U$2") (pin "157") (pinfunction "TDO_157") (pintype "bidirectional"))
    )
    (net (code "147") (name "unconnected-(U$2-TMS-Pad155)") (class "Default")
      (node (ref "U$2") (pin "155") (pinfunction "TMS_155") (pintype "bidirectional"))
    )
    (net (code "148") (name "unconnected-(U$2-VCCINT-Pad13)") (class "Default")
      (node (ref "U$2") (pin "13") (pinfunction "VCCINT_13") (pintype "bidirectional"))
    )
    (net (code "149") (name "unconnected-(U$2-VCCINT-Pad67)") (class "Default")
      (node (ref "U$2") (pin "67") (pinfunction "VCCINT_67") (pintype "bidirectional"))
    )
    (net (code "150") (name "unconnected-(U$2-VCCINT-Pad117)") (class "Default")
      (node (ref "U$2") (pin "117") (pinfunction "VCCINT_117") (pintype "bidirectional"))
    )
    (net (code "151") (name "unconnected-(U$2-VCCINT-Pad170)") (class "Default")
      (node (ref "U$2") (pin "170") (pinfunction "VCCINT_170") (pintype "bidirectional"))
    )
  )
)
